# fredisp.net
KiCad netlist of a schematic drawn in EAGLE
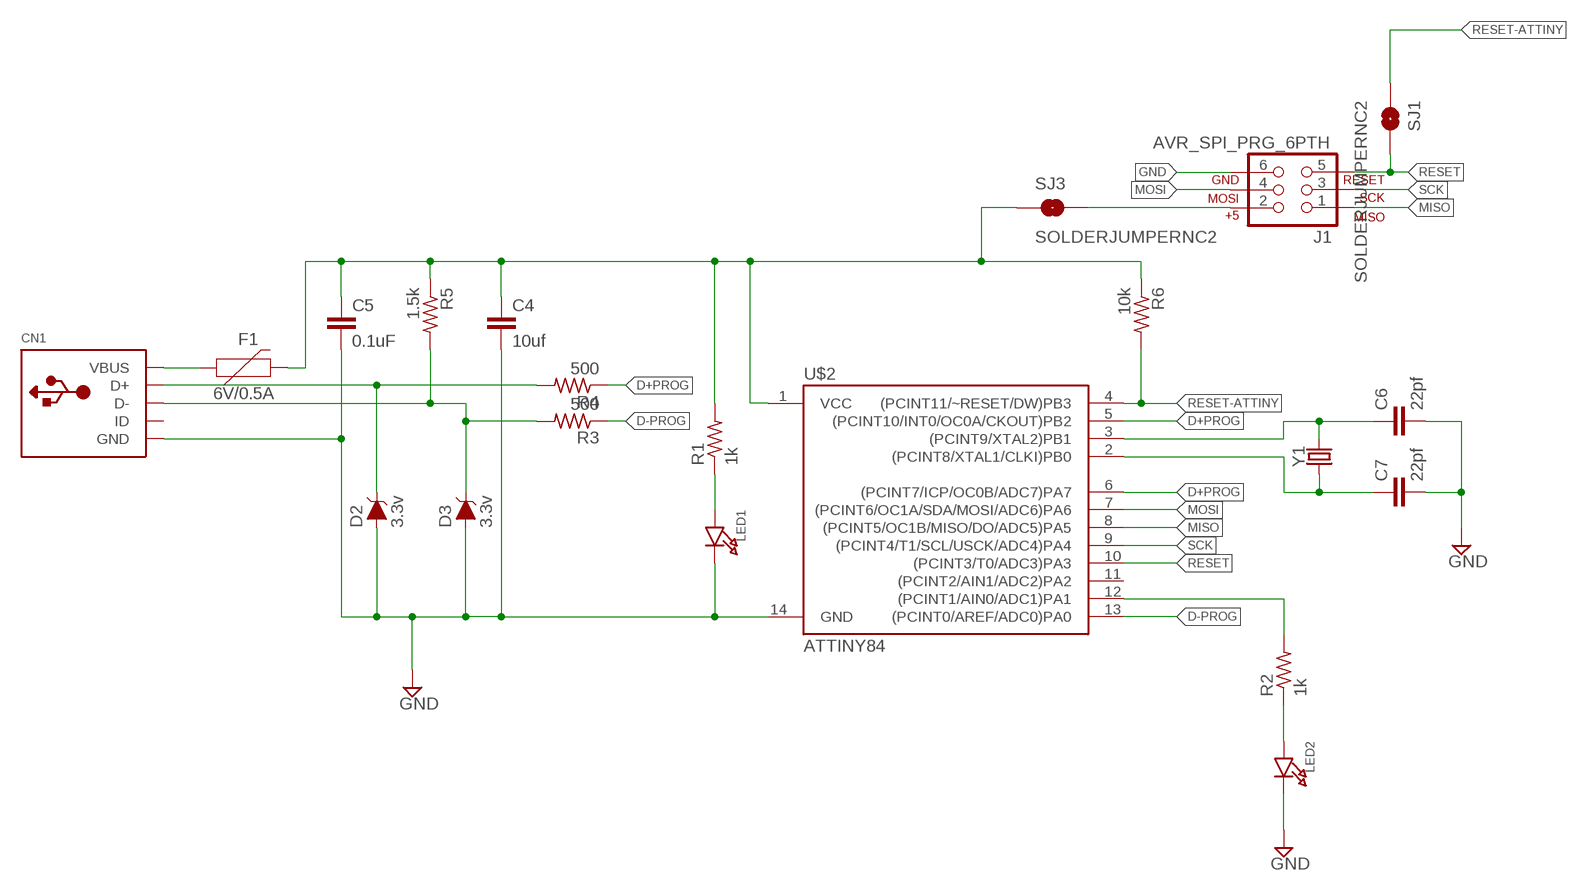
[diagram p0: schematic, sheet 1]

(export (version "E")
  (design (tool "Eeschema 10.0.6"))
  (components
    (comp (ref "C4")
      (value "10uf")
      (footprint "eagle-import:C1206")
      (libsource (lib "eagle-import") (part "C-EUC1206"))
    )
    (comp (ref "C5")
      (value "0.1uF")
      (footprint "eagle-import:C0805")
      (libsource (lib "eagle-import") (part "resistor_C-EUC0805"))
    )
    (comp (ref "C6")
      (value "22pf")
      (footprint "eagle-import:C0805")
      (libsource (lib "eagle-import") (part "resistor_C-EUC0805"))
    )
    (comp (ref "C7")
      (value "22pf")
      (footprint "eagle-import:C0805")
      (libsource (lib "eagle-import") (part "resistor_C-EUC0805"))
    )
    (comp (ref "CN1")
      (value "USBMINIB")
      (footprint "eagle-import:USB-MINIB")
      (libsource (lib "eagle-import") (part "USBMINIB"))
    )
    (comp (ref "D2")
      (value "3.3v")
      (footprint "eagle-import:PANASONIC_SMINI2-F5-B")
      (libsource (lib "eagle-import") (part "DIODE-ZENER-DZ2J150M0L"))
    )
    (comp (ref "D3")
      (value "3.3v")
      (footprint "eagle-import:PANASONIC_SMINI2-F5-B")
      (libsource (lib "eagle-import") (part "DIODE-ZENER-DZ2J150M0L"))
    )
    (comp (ref "F1")
      (value "6V/0.5A")
      (footprint "eagle-import:1206")
      (libsource (lib "eagle-import") (part "PPTC_HALF-AMP"))
    )
    (comp (ref "J1")
      (value "AVR_SPI_PRG_6PTH")
      (footprint "eagle-import:2X3")
      (libsource (lib "eagle-import") (part "AVR_SPI_PRG_6PTH"))
    )
    (comp (ref "LED1")
      (value "LED0805")
      (footprint "eagle-import:CHIPLED_0805")
      (libsource (lib "eagle-import") (part "LED0805"))
    )
    (comp (ref "LED2")
      (value "LED0805")
      (footprint "eagle-import:CHIPLED_0805")
      (libsource (lib "eagle-import") (part "LED0805"))
    )
    (comp (ref "R1")
      (value "1k")
      (footprint "eagle-import:R0805")
      (libsource (lib "eagle-import") (part "R-US_R0805"))
    )
    (comp (ref "R2")
      (value "1k")
      (footprint "eagle-import:R0805")
      (libsource (lib "eagle-import") (part "R-US_R0805"))
    )
    (comp (ref "R3")
      (value "500")
      (footprint "eagle-import:R0805")
      (libsource (lib "eagle-import") (part "R-US_R0805"))
    )
    (comp (ref "R4")
      (value "500")
      (footprint "eagle-import:R0805")
      (libsource (lib "eagle-import") (part "R-US_R0805"))
    )
    (comp (ref "R5")
      (value "1.5k")
      (footprint "eagle-import:R0805")
      (libsource (lib "eagle-import") (part "R-US_R0805"))
    )
    (comp (ref "R6")
      (value "10k")
      (footprint "eagle-import:R0805")
      (libsource (lib "eagle-import") (part "R-US_R0805"))
    )
    (comp (ref "SJ1")
      (value "SOLDERJUMPERNC2")
      (footprint "eagle-import:SJ_2S-NOTRACE")
      (libsource (lib "eagle-import") (part "SOLDERJUMPERNC2"))
    )
    (comp (ref "SJ3")
      (value "SOLDERJUMPERNC2")
      (footprint "eagle-import:SJ_2S-NOTRACE")
      (libsource (lib "eagle-import") (part "SOLDERJUMPERNC2"))
    )
    (comp (ref "U$2")
      (value "ATTINY84")
      (footprint "eagle-import:SO14")
      (libsource (lib "eagle-import") (part "ATTINY84"))
    )
    (comp (ref "Y1")
      (value "CRYSTALSMD-3.2X2.5")
      (footprint "eagle-import:CRYSTAL-SMD-3.2X2.5MM")
      (libsource (lib "eagle-import") (part "CRYSTALSMD-3.2X2.5"))
    )
  )
  (nets
    (net (code "1") (name "/VCC") (class "Default")
      (node (ref "C4") (pin "1") (pinfunction "1_1") (pintype "passive"))
      (node (ref "C5") (pin "1") (pinfunction "1_1") (pintype "passive"))
      (node (ref "F1") (pin "2") (pinfunction "2_2") (pintype "bidirectional"))
      (node (ref "R1") (pin "2") (pinfunction "2_2") (pintype "passive"))
      (node (ref "R5") (pin "1") (pinfunction "1_1") (pintype "passive"))
      (node (ref "R6") (pin "1") (pinfunction "1_1") (pintype "passive"))
      (node (ref "SJ3") (pin "1") (pinfunction "1_1") (pintype "passive"))
      (node (ref "U$2") (pin "1") (pinfunction "VCC_1") (pintype "bidirectional"))
    )
    (net (code "2") (name "D+PROG") (class "Default")
      (node (ref "R4") (pin "1") (pinfunction "1_1") (pintype "passive"))
      (node (ref "U$2") (pin "5") (pinfunction "(PCINT10/INT0/OC0A/CKOUT)PB2_5") (pintype "bidirectional"))
      (node (ref "U$2") (pin "6") (pinfunction "(PCINT7/ICP/OC0B/ADC7)PA7_6") (pintype "bidirectional"))
    )
    (net (code "3") (name "D-PROG") (class "Default")
      (node (ref "R3") (pin "1") (pinfunction "1_1") (pintype "passive"))
      (node (ref "U$2") (pin "13") (pinfunction "(PCINT0/AREF/ADC0)PA0_13") (pintype "bidirectional"))
    )
    (net (code "4") (name "GND") (class "Default")
      (node (ref "C4") (pin "2") (pinfunction "2_2") (pintype "passive"))
      (node (ref "C5") (pin "2") (pinfunction "2_2") (pintype "passive"))
      (node (ref "C6") (pin "2") (pinfunction "2_2") (pintype "passive"))
      (node (ref "C7") (pin "2") (pinfunction "2_2") (pintype "passive"))
      (node (ref "CN1") (pin "GND") (pinfunction "GND_GND") (pintype "power_in"))
      (node (ref "D2") (pin "A") (pinfunction "A_A") (pintype "passive"))
      (node (ref "D3") (pin "A") (pinfunction "A_A") (pintype "passive"))
      (node (ref "J1") (pin "6") (pinfunction "6_6") (pintype "passive"))
      (node (ref "LED1") (pin "C") (pinfunction "C_C") (pintype "passive"))
      (node (ref "LED2") (pin "C") (pinfunction "C_C") (pintype "passive"))
      (node (ref "U$2") (pin "14") (pinfunction "GND_14") (pintype "bidirectional"))
    )
    (net (code "5") (name "MISO") (class "Default")
      (node (ref "J1") (pin "1") (pinfunction "1_1") (pintype "passive"))
      (node (ref "U$2") (pin "8") (pinfunction "(PCINT5/OC1B/MISO/DO/ADC5)PA5_8") (pintype "bidirectional"))
    )
    (net (code "6") (name "MOSI") (class "Default")
      (node (ref "J1") (pin "4") (pinfunction "4_4") (pintype "passive"))
      (node (ref "U$2") (pin "7") (pinfunction "(PCINT6/OC1A/SDA/MOSI/ADC6)PA6_7") (pintype "bidirectional"))
    )
    (net (code "7") (name "Net-(CN1-PadD+)") (class "Default")
      (node (ref "CN1") (pin "D+") (pinfunction "D+_D+") (pintype "bidirectional"))
      (node (ref "D2") (pin "C") (pinfunction "C_C") (pintype "passive"))
      (node (ref "R4") (pin "2") (pinfunction "2_2") (pintype "passive"))
    )
    (net (code "8") (name "Net-(CN1-PadD-)") (class "Default")
      (node (ref "CN1") (pin "D-") (pinfunction "D-_D-") (pintype "bidirectional"))
      (node (ref "D3") (pin "C") (pinfunction "C_C") (pintype "passive"))
      (node (ref "R3") (pin "2") (pinfunction "2_2") (pintype "passive"))
      (node (ref "R5") (pin "2") (pinfunction "2_2") (pintype "passive"))
    )
    (net (code "9") (name "Net-(CN1-PadVBUS)") (class "Default")
      (node (ref "CN1") (pin "VBUS") (pinfunction "VBUS_VBUS") (pintype "power_in"))
      (node (ref "F1") (pin "1") (pinfunction "1_1") (pintype "bidirectional"))
    )
    (net (code "10") (name "Net-(J1-Pad2)") (class "Default")
      (node (ref "J1") (pin "2") (pinfunction "2_2") (pintype "passive"))
      (node (ref "SJ3") (pin "2") (pinfunction "2_2") (pintype "passive"))
    )
    (net (code "11") (name "Net-(LED1-PadA)") (class "Default")
      (node (ref "LED1") (pin "A") (pinfunction "A_A") (pintype "passive"))
      (node (ref "R1") (pin "1") (pinfunction "1_1") (pintype "passive"))
    )
    (net (code "12") (name "Net-(LED2-PadA)") (class "Default")
      (node (ref "LED2") (pin "A") (pinfunction "A_A") (pintype "passive"))
      (node (ref "R2") (pin "1") (pinfunction "1_1") (pintype "passive"))
    )
    (net (code "13") (name "Net-(U$2-(PCINT1{slash}AIN0{slash}ADC1)PA1)") (class "Default")
      (node (ref "R2") (pin "2") (pinfunction "2_2") (pintype "passive"))
      (node (ref "U$2") (pin "12") (pinfunction "(PCINT1/AIN0/ADC1)PA1_12") (pintype "bidirectional"))
    )
    (net (code "14") (name "Net-(U$2-(PCINT8{slash}XTAL1{slash}CLKI)PB0)") (class "Default")
      (node (ref "C7") (pin "1") (pinfunction "1_1") (pintype "passive"))
      (node (ref "U$2") (pin "2") (pinfunction "(PCINT8/XTAL1/CLKI)PB0_2") (pintype "bidirectional"))
      (node (ref "Y1") (pin "1") (pinfunction "1_1") (pintype "passive"))
    )
    (net (code "15") (name "Net-(U$2-(PCINT9{slash}XTAL2)PB1)") (class "Default")
      (node (ref "C6") (pin "1") (pinfunction "1_1") (pintype "passive"))
      (node (ref "U$2") (pin "3") (pinfunction "(PCINT9/XTAL2)PB1_3") (pintype "bidirectional"))
      (node (ref "Y1") (pin "3") (pinfunction "2_3") (pintype "passive"))
    )
    (net (code "16") (name "RESET") (class "Default")
      (node (ref "J1") (pin "5") (pinfunction "5_5") (pintype "passive"))
      (node (ref "SJ1") (pin "2") (pinfunction "2_2") (pintype "passive"))
      (node (ref "U$2") (pin "10") (pinfunction "(PCINT3/T0/ADC3)PA3_10") (pintype "bidirectional"))
    )
    (net (code "17") (name "RESET-ATTINY") (class "Default")
      (node (ref "R6") (pin "2") (pinfunction "2_2") (pintype "passive"))
      (node (ref "SJ1") (pin "1") (pinfunction "1_1") (pintype "passive"))
      (node (ref "U$2") (pin "4") (pinfunction "(PCINT11/~{RESET/DW})PB3_4") (pintype "bidirectional"))
    )
    (net (code "18") (name "SCK") (class "Default")
      (node (ref "J1") (pin "3") (pinfunction "3_3") (pintype "passive"))
      (node (ref "U$2") (pin "9") (pinfunction "(PCINT4/T1/SCL/USCK/ADC4)PA4_9") (pintype "bidirectional"))
    )
    (net (code "19") (name "unconnected-(CN1-PadID)") (class "Default")
      (node (ref "CN1") (pin "ID") (pinfunction "ID_ID") (pintype "bidirectional"))
    )
    (net (code "20") (name "unconnected-(U$2-(PCINT2{slash}AIN1{slash}ADC2)PA2-Pad11)") (class "Default")
      (node (ref "U$2") (pin "11") (pinfunction "(PCINT2/AIN1/ADC2)PA2_11") (pintype "bidirectional"))
    )
  )
)
